# irng_2_0.net
KiCad netlist of a schematic drawn in EAGLE
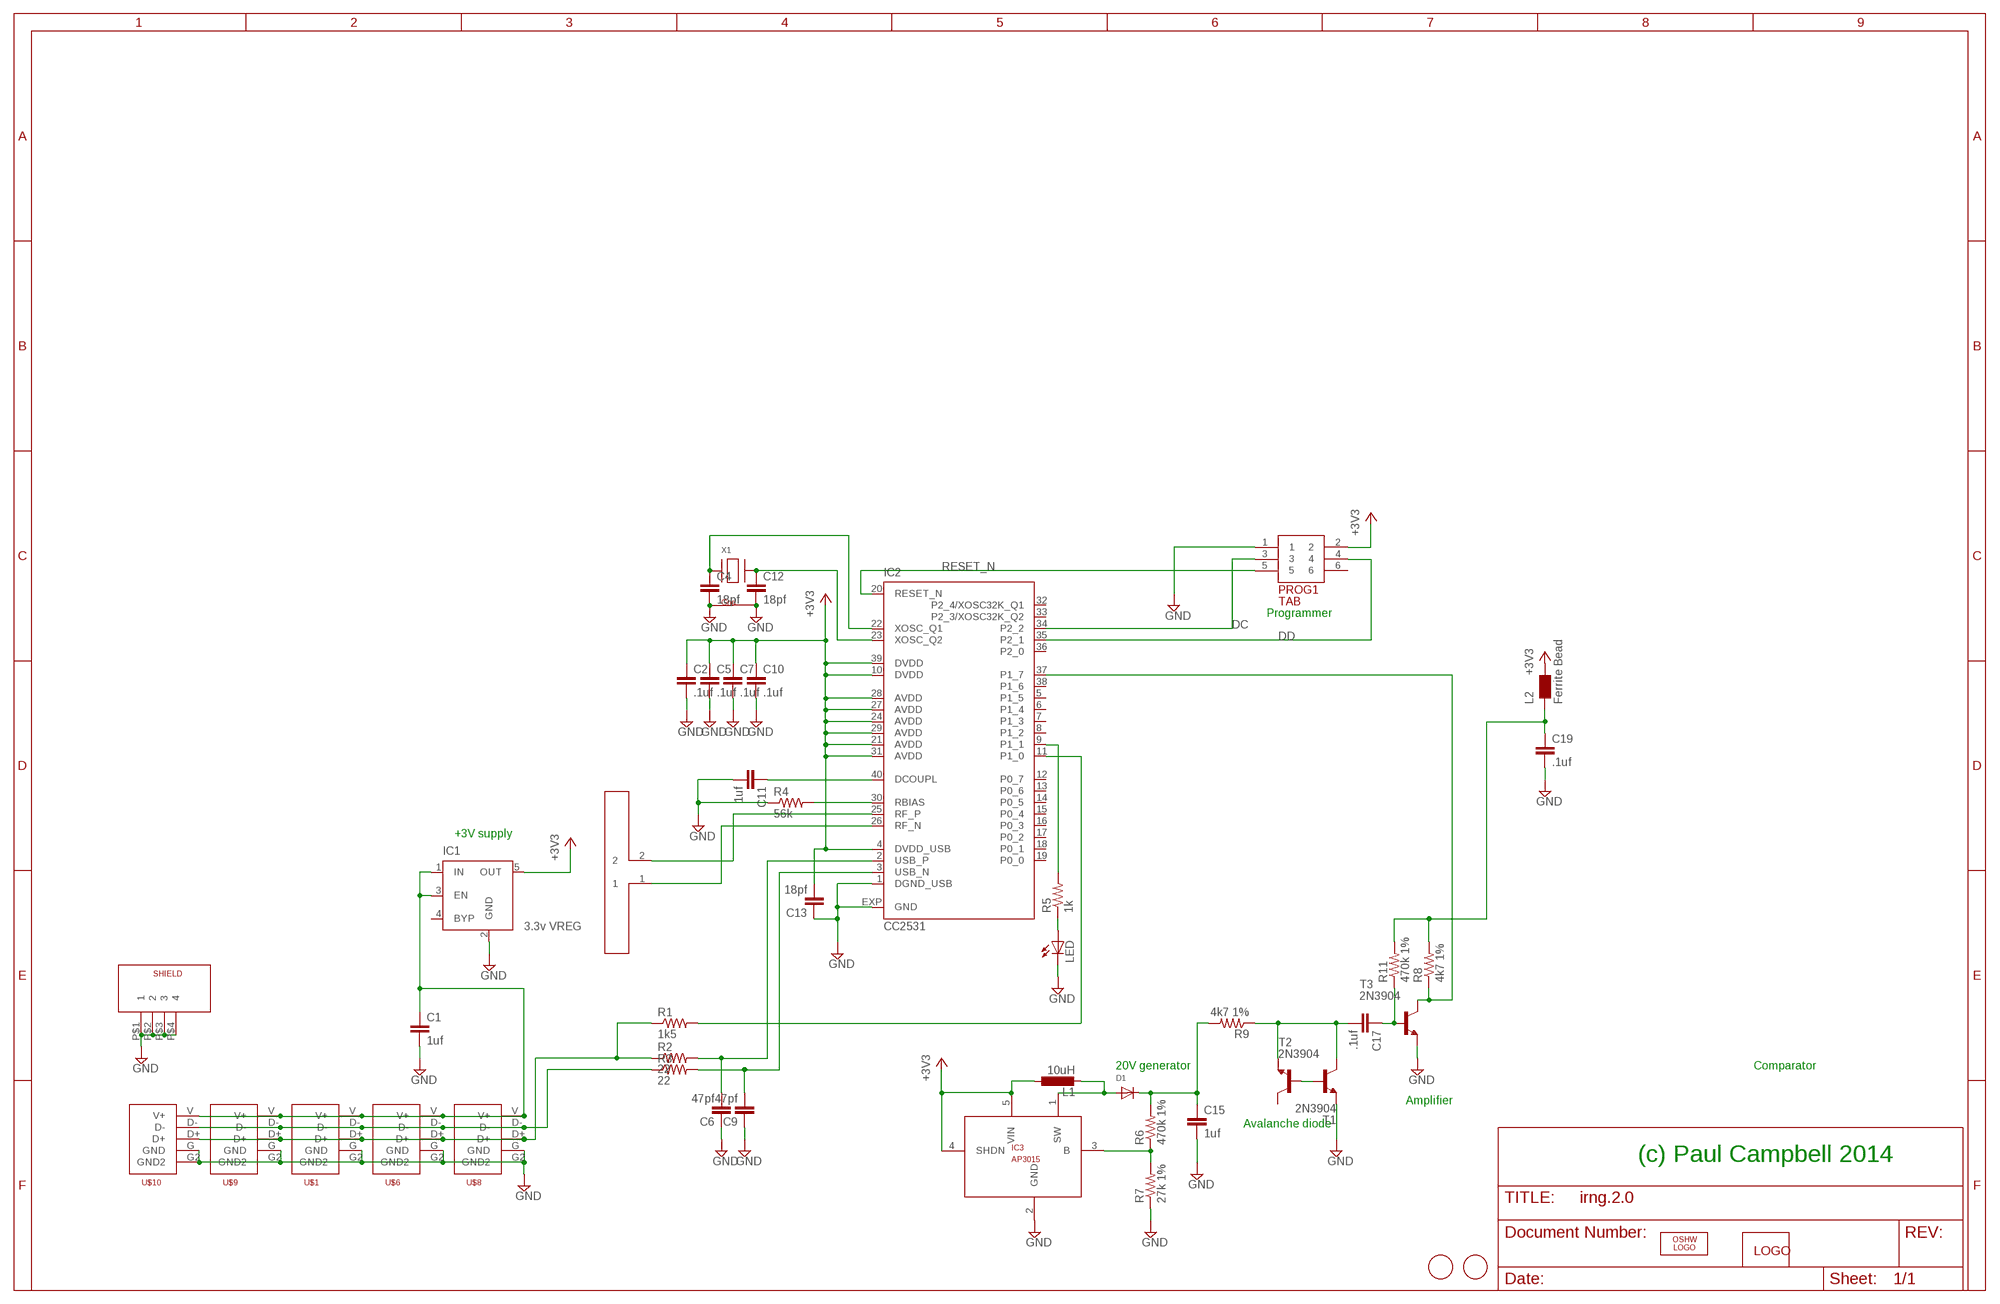
[diagram p0: schematic, sheet 1]

(export (version "E")
  (design (tool "Eeschema 10.0.6"))
  (components
    (comp (ref "C1")
      (value "1uf")
      (footprint "eagle-import:C0603")
      (libsource (lib "eagle-import") (part "C-EUC0603"))
    )
    (comp (ref "C2")
      (value ".1uf")
      (footprint "eagle-import:C0603")
      (libsource (lib "eagle-import") (part "C-EUC0603"))
    )
    (comp (ref "C4")
      (value "18pf")
      (footprint "eagle-import:C0603")
      (libsource (lib "eagle-import") (part "C-EUC0603"))
    )
    (comp (ref "C5")
      (value ".1uf")
      (footprint "eagle-import:C0603K")
      (libsource (lib "eagle-import") (part "C-EUC0603K"))
    )
    (comp (ref "C6")
      (value "47pf")
      (footprint "eagle-import:C0603")
      (libsource (lib "eagle-import") (part "C-EUC0603"))
    )
    (comp (ref "C7")
      (value ".1uf")
      (footprint "eagle-import:C0603")
      (libsource (lib "eagle-import") (part "C-EUC0603"))
    )
    (comp (ref "C9")
      (value "47pf")
      (footprint "eagle-import:C0603")
      (libsource (lib "eagle-import") (part "C-EUC0603"))
    )
    (comp (ref "C10")
      (value ".1uf")
      (footprint "eagle-import:C0603")
      (libsource (lib "eagle-import") (part "C-EUC0603"))
    )
    (comp (ref "C11")
      (value "1uf")
      (footprint "eagle-import:C0603")
      (libsource (lib "eagle-import") (part "C-EUC0603"))
    )
    (comp (ref "C12")
      (value "18pf")
      (footprint "eagle-import:C0603")
      (libsource (lib "eagle-import") (part "C-EUC0603"))
    )
    (comp (ref "C13")
      (value "18pf")
      (footprint "eagle-import:C0603")
      (libsource (lib "eagle-import") (part "C-EUC0603"))
    )
    (comp (ref "C15")
      (value "1uf")
      (footprint "eagle-import:C0603")
      (libsource (lib "eagle-import") (part "C-EUC0603"))
    )
    (comp (ref "C17")
      (value ".1uf")
      (footprint "eagle-import:C0603")
      (libsource (lib "eagle-import") (part "C-EUC0603"))
    )
    (comp (ref "C19")
      (value ".1uf")
      (footprint "eagle-import:C0603")
      (libsource (lib "eagle-import") (part "C-EUC0603"))
    )
    (comp (ref "D1")
      (value "DIODESOD-323F")
      (footprint "eagle-import:SOD-323F")
      (libsource (lib "eagle-import") (part "DIODESOD-323F"))
    )
    (comp (ref "IC1")
      (value "3.3v VREG")
      (footprint "eagle-import:SOT23-5")
      (libsource (lib "eagle-import") (part "MIC5219XX"))
    )
    (comp (ref "IC2")
      (value "CC2531")
      (footprint "eagle-import:RHA_S-PVQFN-N40")
      (fields (field (name "MPN") "CC2531F256RHAT"))
      (libsource (lib "eagle-import") (part "CC2531"))
    )
    (comp (ref "IC3")
      (value "AP3015")
      (footprint "eagle-import:SOT23-5")
      (libsource (lib "eagle-import") (part "AP3105"))
    )
    (comp (ref "L1")
      (value "10uH")
      (footprint "eagle-import:L2012C")
      (libsource (lib "eagle-import") (part "L-EUL2012C"))
    )
    (comp (ref "L2")
      (value "Ferrite Bead")
      (footprint "eagle-import:0603")
      (libsource (lib "eagle-import") (part "WE-CBF_0603"))
    )
    (comp (ref "LED")
      (value "LEDCHIP-LED0805")
      (footprint "eagle-import:CHIP-LED0805")
      (libsource (lib "eagle-import") (part "LEDCHIP-LED0805"))
    )
    (comp (ref "LOGO1")
      (value "OSHW_LOGO_FILLX0100-NT")
      (footprint "eagle-import:OSHW_FILLX100_NOTEXT")
      (libsource (lib "eagle-import") (part "OSHW_LOGO_FILLX0100-NT"))
    )
    (comp (ref "PROG1")
      (value "TAB")
      (footprint "eagle-import:TAG")
      (libsource (lib "eagle-import") (part "TAB"))
    )
    (comp (ref "R1")
      (value "1k5")
      (footprint "eagle-import:R0603")
      (libsource (lib "eagle-import") (part "R-US_R0603"))
    )
    (comp (ref "R2")
      (value "22")
      (footprint "eagle-import:R0603")
      (libsource (lib "eagle-import") (part "R-US_R0603"))
    )
    (comp (ref "R3")
      (value "22")
      (footprint "eagle-import:R0603")
      (libsource (lib "eagle-import") (part "R-US_R0603"))
    )
    (comp (ref "R4")
      (value "56k")
      (footprint "eagle-import:R0603")
      (libsource (lib "eagle-import") (part "R-US_R0603"))
    )
    (comp (ref "R5")
      (value "1k")
      (footprint "eagle-import:R0603")
      (libsource (lib "eagle-import") (part "R-US_R0603"))
    )
    (comp (ref "R6")
      (value "470k 1%")
      (footprint "eagle-import:R0603")
      (libsource (lib "eagle-import") (part "R-US_R0603"))
    )
    (comp (ref "R7")
      (value "27k 1%")
      (footprint "eagle-import:R0603")
      (libsource (lib "eagle-import") (part "R-US_R0603"))
    )
    (comp (ref "R8")
      (value "4k7 1%")
      (footprint "eagle-import:R0603")
      (libsource (lib "eagle-import") (part "R-US_R0603"))
    )
    (comp (ref "R9")
      (value "4k7 1%")
      (footprint "eagle-import:R0603")
      (libsource (lib "eagle-import") (part "R-US_R0603"))
    )
    (comp (ref "R11")
      (value "470k 1%")
      (footprint "eagle-import:R0603")
      (libsource (lib "eagle-import") (part "R-US_R0603"))
    )
    (comp (ref "T1")
      (value "2N3904")
      (footprint "eagle-import:SOT23-BEC")
      (libsource (lib "eagle-import") (part "-NPN-SOT23-BECBCF32"))
    )
    (comp (ref "T2")
      (value "2N3904")
      (footprint "eagle-import:SOT23-BEC")
      (libsource (lib "eagle-import") (part "-NPN-SOT23-BECBCF32"))
    )
    (comp (ref "T3")
      (value "2N3904")
      (footprint "eagle-import:SOT23-BEC")
      (libsource (lib "eagle-import") (part "-NPN-SOT23-BECBCF32"))
    )
    (comp (ref "U$1")
      (value "USBPAD")
      (footprint "eagle-import:PAD4")
      (libsource (lib "eagle-import") (part "USBPAD"))
    )
    (comp (ref "U$2")
      (value "DIPOLE")
      (footprint "eagle-import:YSHORT-DIPOLE")
      (libsource (lib "eagle-import") (part "DIPOLE"))
    )
    (comp (ref "U$3")
      (value "FIDUCIAL")
      (footprint "eagle-import:FIDUCIAL_1MM")
      (libsource (lib "eagle-import") (part "FIDUCIAL"))
    )
    (comp (ref "U$4")
      (value "FIDUCIAL")
      (footprint "eagle-import:FIDUCIAL_1MM")
      (libsource (lib "eagle-import") (part "FIDUCIAL"))
    )
    (comp (ref "U$5")
      (value "MOONBASE-LOGO")
      (footprint "eagle-import:MOONBASE-LOGO")
      (libsource (lib "eagle-import") (part "MOONBASE-LOGO"))
    )
    (comp (ref "U$6")
      (value "USBPAD")
      (footprint "eagle-import:PAD4")
      (libsource (lib "eagle-import") (part "USBPAD"))
    )
    (comp (ref "U$7")
      (value "SHIELD-NEW")
      (footprint "eagle-import:SHIELD-NEW")
      (libsource (lib "eagle-import") (part "SHIELD-NEW"))
    )
    (comp (ref "U$8")
      (value "USBPAD")
      (footprint "eagle-import:PAD4")
      (libsource (lib "eagle-import") (part "USBPAD"))
    )
    (comp (ref "U$9")
      (value "USBPAD")
      (footprint "eagle-import:PAD4")
      (libsource (lib "eagle-import") (part "USBPAD"))
    )
    (comp (ref "U$10")
      (value "USBPAD")
      (footprint "eagle-import:PAD4")
      (libsource (lib "eagle-import") (part "USBPAD"))
    )
    (comp (ref "X1")
      (value "XTAL-4-3225")
      (footprint "eagle-import:NX3225")
      (libsource (lib "eagle-import") (part "XTAL-4-3225"))
    )
  )
  (nets
    (net (code "1") (name "+3V3") (class "Default")
      (node (ref "C10") (pin "1") (pinfunction "1_1") (pintype "passive"))
      (node (ref "C13") (pin "2") (pinfunction "2_2") (pintype "passive"))
      (node (ref "C2") (pin "1") (pinfunction "1_1") (pintype "passive"))
      (node (ref "C5") (pin "1") (pinfunction "1_1") (pintype "passive"))
      (node (ref "C7") (pin "1") (pinfunction "1_1") (pintype "passive"))
      (node (ref "IC1") (pin "5") (pinfunction "OUT_5") (pintype "output"))
      (node (ref "IC2") (pin "10") (pinfunction "DVDD_10") (pintype "power_in"))
      (node (ref "IC2") (pin "21") (pinfunction "AVDD_21") (pintype "power_in"))
      (node (ref "IC2") (pin "24") (pinfunction "AVDD_24") (pintype "power_in"))
      (node (ref "IC2") (pin "27") (pinfunction "AVDD_27") (pintype "power_in"))
      (node (ref "IC2") (pin "28") (pinfunction "AVDD_28") (pintype "power_in"))
      (node (ref "IC2") (pin "29") (pinfunction "AVDD_29") (pintype "power_in"))
      (node (ref "IC2") (pin "31") (pinfunction "AVDD_31") (pintype "power_in"))
      (node (ref "IC2") (pin "39") (pinfunction "DVDD_39") (pintype "power_in"))
      (node (ref "IC2") (pin "4") (pinfunction "DVDD_USB_4") (pintype "power_in"))
      (node (ref "IC3") (pin "4") (pinfunction "SHDN_4") (pintype "bidirectional"))
      (node (ref "IC3") (pin "5") (pinfunction "VIN_5") (pintype "bidirectional"))
      (node (ref "L1") (pin "1") (pinfunction "1_1") (pintype "passive"))
      (node (ref "L2") (pin "2") (pinfunction "2_2") (pintype "passive"))
      (node (ref "PROG1") (pin "2") (pinfunction "2_2") (pintype "bidirectional"))
    )
    (net (code "2") (name "/DC") (class "Default")
      (node (ref "IC2") (pin "34") (pinfunction "P2_2_34") (pintype "bidirectional"))
      (node (ref "PROG1") (pin "3") (pinfunction "3_3") (pintype "bidirectional"))
    )
    (net (code "3") (name "/DD") (class "Default")
      (node (ref "IC2") (pin "35") (pinfunction "P2_1_35") (pintype "bidirectional"))
      (node (ref "PROG1") (pin "4") (pinfunction "4_4") (pintype "bidirectional"))
    )
    (net (code "4") (name "/RESET_N") (class "Default")
      (node (ref "IC2") (pin "20") (pinfunction "RESET_N_20") (pintype "input"))
      (node (ref "PROG1") (pin "5") (pinfunction "5_5") (pintype "bidirectional"))
    )
    (net (code "5") (name "GND") (class "Default")
      (node (ref "C1") (pin "2") (pinfunction "2_2") (pintype "passive"))
      (node (ref "C10") (pin "2") (pinfunction "2_2") (pintype "passive"))
      (node (ref "C11") (pin "2") (pinfunction "2_2") (pintype "passive"))
      (node (ref "C12") (pin "2") (pinfunction "2_2") (pintype "passive"))
      (node (ref "C13") (pin "1") (pinfunction "1_1") (pintype "passive"))
      (node (ref "C15") (pin "2") (pinfunction "2_2") (pintype "passive"))
      (node (ref "C19") (pin "2") (pinfunction "2_2") (pintype "passive"))
      (node (ref "C2") (pin "2") (pinfunction "2_2") (pintype "passive"))
      (node (ref "C4") (pin "2") (pinfunction "2_2") (pintype "passive"))
      (node (ref "C5") (pin "2") (pinfunction "2_2") (pintype "passive"))
      (node (ref "C6") (pin "1") (pinfunction "1_1") (pintype "passive"))
      (node (ref "C7") (pin "2") (pinfunction "2_2") (pintype "passive"))
      (node (ref "C9") (pin "1") (pinfunction "1_1") (pintype "passive"))
      (node (ref "IC1") (pin "2") (pinfunction "GND_2") (pintype "power_in"))
      (node (ref "IC2") (pin "1") (pinfunction "DGND_USB_1") (pintype "power_in"))
      (node (ref "IC2") (pin "EXP") (pinfunction "GND_EXP") (pintype "passive"))
      (node (ref "IC3") (pin "2") (pinfunction "GND_2") (pintype "bidirectional"))
      (node (ref "LED") (pin "C") (pinfunction "C_C") (pintype "passive"))
      (node (ref "PROG1") (pin "1") (pinfunction "1_1") (pintype "bidirectional"))
      (node (ref "R4") (pin "1") (pinfunction "1_1") (pintype "passive"))
      (node (ref "R7") (pin "1") (pinfunction "1_1") (pintype "passive"))
      (node (ref "T2") (pin "E") (pinfunction "E_E") (pintype "passive"))
      (node (ref "T3") (pin "E") (pinfunction "E_E") (pintype "passive"))
      (node (ref "U$1") (pin "G") (pinfunction "GND_G") (pintype "bidirectional"))
      (node (ref "U$1") (pin "G2") (pinfunction "GND2_G2") (pintype "bidirectional"))
      (node (ref "U$10") (pin "G") (pinfunction "GND_G") (pintype "bidirectional"))
      (node (ref "U$10") (pin "G2") (pinfunction "GND2_G2") (pintype "bidirectional"))
      (node (ref "U$6") (pin "G") (pinfunction "GND_G") (pintype "bidirectional"))
      (node (ref "U$6") (pin "G2") (pinfunction "GND2_G2") (pintype "bidirectional"))
      (node (ref "U$7") (pin "P$1") (pinfunction "1_P$1") (pintype "bidirectional"))
      (node (ref "U$7") (pin "P$2") (pinfunction "2_P$2") (pintype "bidirectional"))
      (node (ref "U$7") (pin "P$3") (pinfunction "3_P$3") (pintype "bidirectional"))
      (node (ref "U$7") (pin "P$4") (pinfunction "4_P$4") (pintype "bidirectional"))
      (node (ref "U$8") (pin "G") (pinfunction "GND_G") (pintype "bidirectional"))
      (node (ref "U$8") (pin "G2") (pinfunction "GND2_G2") (pintype "bidirectional"))
      (node (ref "U$9") (pin "G") (pinfunction "GND_G") (pintype "bidirectional"))
      (node (ref "U$9") (pin "G2") (pinfunction "GND2_G2") (pintype "bidirectional"))
      (node (ref "X1") (pin "2") (pinfunction "G2_2") (pintype "power_in"))
      (node (ref "X1") (pin "4") (pinfunction "G1_4") (pintype "power_in"))
    )
    (net (code "6") (name "Net-(C15-Pad1)") (class "Default")
      (node (ref "C15") (pin "1") (pinfunction "1_1") (pintype "passive"))
      (node (ref "D1") (pin "C") (pinfunction "C_C") (pintype "passive"))
      (node (ref "R6") (pin "2") (pinfunction "2_2") (pintype "passive"))
      (node (ref "R9") (pin "2") (pinfunction "2_2") (pintype "passive"))
    )
    (net (code "7") (name "Net-(C17-Pad1)") (class "Default")
      (node (ref "C17") (pin "1") (pinfunction "1_1") (pintype "passive"))
      (node (ref "R11") (pin "1") (pinfunction "1_1") (pintype "passive"))
      (node (ref "T3") (pin "B") (pinfunction "B_B") (pintype "passive"))
    )
    (net (code "8") (name "Net-(C17-Pad2)") (class "Default")
      (node (ref "C17") (pin "2") (pinfunction "2_2") (pintype "passive"))
      (node (ref "R9") (pin "1") (pinfunction "1_1") (pintype "passive"))
      (node (ref "T1") (pin "E") (pinfunction "E_E") (pintype "passive"))
      (node (ref "T2") (pin "C") (pinfunction "C_C") (pintype "passive"))
    )
    (net (code "9") (name "Net-(C19-Pad1)") (class "Default")
      (node (ref "C19") (pin "1") (pinfunction "1_1") (pintype "passive"))
      (node (ref "L2") (pin "1") (pinfunction "1_1") (pintype "passive"))
      (node (ref "R11") (pin "2") (pinfunction "2_2") (pintype "passive"))
      (node (ref "R8") (pin "2") (pinfunction "2_2") (pintype "passive"))
    )
    (net (code "10") (name "Net-(IC1-EN)") (class "Default")
      (node (ref "C1") (pin "1") (pinfunction "1_1") (pintype "passive"))
      (node (ref "IC1") (pin "1") (pinfunction "IN_1") (pintype "input"))
      (node (ref "IC1") (pin "3") (pinfunction "EN_3") (pintype "input"))
      (node (ref "U$1") (pin "V") (pinfunction "V+_V") (pintype "bidirectional"))
      (node (ref "U$10") (pin "V") (pinfunction "V+_V") (pintype "bidirectional"))
      (node (ref "U$6") (pin "V") (pinfunction "V+_V") (pintype "bidirectional"))
      (node (ref "U$8") (pin "V") (pinfunction "V+_V") (pintype "bidirectional"))
      (node (ref "U$9") (pin "V") (pinfunction "V+_V") (pintype "bidirectional"))
    )
    (net (code "11") (name "Net-(IC2-DCOUPL)") (class "Default")
      (node (ref "C11") (pin "1") (pinfunction "1_1") (pintype "passive"))
      (node (ref "IC2") (pin "40") (pinfunction "DCOUPL_40") (pintype "power_in"))
    )
    (net (code "12") (name "Net-(IC2-P1_0)") (class "Default")
      (node (ref "IC2") (pin "11") (pinfunction "P1_0_11") (pintype "bidirectional"))
      (node (ref "R1") (pin "2") (pinfunction "2_2") (pintype "passive"))
    )
    (net (code "13") (name "Net-(IC2-P1_1)") (class "Default")
      (node (ref "IC2") (pin "9") (pinfunction "P1_1_9") (pintype "bidirectional"))
      (node (ref "R5") (pin "2") (pinfunction "2_2") (pintype "passive"))
    )
    (net (code "14") (name "Net-(IC2-P1_7)") (class "Default")
      (node (ref "IC2") (pin "37") (pinfunction "P1_7_37") (pintype "bidirectional"))
      (node (ref "R8") (pin "1") (pinfunction "1_1") (pintype "passive"))
      (node (ref "T3") (pin "C") (pinfunction "C_C") (pintype "passive"))
    )
    (net (code "15") (name "Net-(IC2-RBIAS)") (class "Default")
      (node (ref "IC2") (pin "30") (pinfunction "RBIAS_30") (pintype "bidirectional"))
      (node (ref "R4") (pin "2") (pinfunction "2_2") (pintype "passive"))
    )
    (net (code "16") (name "Net-(IC2-RF_N)") (class "Default")
      (node (ref "IC2") (pin "26") (pinfunction "RF_N_26") (pintype "bidirectional"))
      (node (ref "U$2") (pin "1") (pinfunction "1_1") (pintype "bidirectional"))
    )
    (net (code "17") (name "Net-(IC2-RF_P)") (class "Default")
      (node (ref "IC2") (pin "25") (pinfunction "RF_P_25") (pintype "bidirectional"))
      (node (ref "U$2") (pin "2") (pinfunction "2_2") (pintype "bidirectional"))
    )
    (net (code "18") (name "Net-(IC2-USB_N)") (class "Default")
      (node (ref "C9") (pin "2") (pinfunction "2_2") (pintype "passive"))
      (node (ref "IC2") (pin "3") (pinfunction "USB_N_3") (pintype "bidirectional"))
      (node (ref "R3") (pin "2") (pinfunction "2_2") (pintype "passive"))
    )
    (net (code "19") (name "Net-(IC2-USB_P)") (class "Default")
      (node (ref "C6") (pin "2") (pinfunction "2_2") (pintype "passive"))
      (node (ref "IC2") (pin "2") (pinfunction "USB_P_2") (pintype "bidirectional"))
      (node (ref "R2") (pin "2") (pinfunction "2_2") (pintype "passive"))
    )
    (net (code "20") (name "Net-(IC2-XOSC_Q1)") (class "Default")
      (node (ref "C4") (pin "1") (pinfunction "1_1") (pintype "passive"))
      (node (ref "IC2") (pin "22") (pinfunction "XOSC_Q1_22") (pintype "bidirectional"))
      (node (ref "X1") (pin "1") (pinfunction "X1_1") (pintype "bidirectional"))
    )
    (net (code "21") (name "Net-(IC2-XOSC_Q2)") (class "Default")
      (node (ref "C12") (pin "1") (pinfunction "1_1") (pintype "passive"))
      (node (ref "IC2") (pin "23") (pinfunction "XOSC_Q2_23") (pintype "bidirectional"))
      (node (ref "X1") (pin "3") (pinfunction "X2_3") (pintype "bidirectional"))
    )
    (net (code "22") (name "Net-(IC3-B)") (class "Default")
      (node (ref "IC3") (pin "3") (pinfunction "B_3") (pintype "bidirectional"))
      (node (ref "R6") (pin "1") (pinfunction "1_1") (pintype "passive"))
      (node (ref "R7") (pin "2") (pinfunction "2_2") (pintype "passive"))
    )
    (net (code "23") (name "Net-(IC3-SW)") (class "Default")
      (node (ref "D1") (pin "A") (pinfunction "A_A") (pintype "passive"))
      (node (ref "IC3") (pin "1") (pinfunction "SW_1") (pintype "bidirectional"))
      (node (ref "L1") (pin "2") (pinfunction "2_2") (pintype "passive"))
    )
    (net (code "24") (name "Net-(LED-PadA)") (class "Default")
      (node (ref "LED") (pin "A") (pinfunction "A_A") (pintype "passive"))
      (node (ref "R5") (pin "1") (pinfunction "1_1") (pintype "passive"))
    )
    (net (code "25") (name "Net-(R1-Pad1)") (class "Default")
      (node (ref "R1") (pin "1") (pinfunction "1_1") (pintype "passive"))
      (node (ref "R2") (pin "1") (pinfunction "1_1") (pintype "passive"))
      (node (ref "U$1") (pin "D+") (pinfunction "D+_D+") (pintype "bidirectional"))
      (node (ref "U$10") (pin "D+") (pinfunction "D+_D+") (pintype "bidirectional"))
      (node (ref "U$6") (pin "D+") (pinfunction "D+_D+") (pintype "bidirectional"))
      (node (ref "U$8") (pin "D+") (pinfunction "D+_D+") (pintype "bidirectional"))
      (node (ref "U$9") (pin "D+") (pinfunction "D+_D+") (pintype "bidirectional"))
    )
    (net (code "26") (name "Net-(R3-Pad1)") (class "Default")
      (node (ref "R3") (pin "1") (pinfunction "1_1") (pintype "passive"))
      (node (ref "U$1") (pin "D-") (pinfunction "D-_D-") (pintype "bidirectional"))
      (node (ref "U$10") (pin "D-") (pinfunction "D-_D-") (pintype "bidirectional"))
      (node (ref "U$6") (pin "D-") (pinfunction "D-_D-") (pintype "bidirectional"))
      (node (ref "U$8") (pin "D-") (pinfunction "D-_D-") (pintype "bidirectional"))
      (node (ref "U$9") (pin "D-") (pinfunction "D-_D-") (pintype "bidirectional"))
    )
    (net (code "27") (name "Net-(T1-PadB)") (class "Default")
      (node (ref "T1") (pin "B") (pinfunction "B_B") (pintype "passive"))
      (node (ref "T2") (pin "B") (pinfunction "B_B") (pintype "passive"))
    )
    (net (code "28") (name "unconnected-(IC1-BYP-Pad4)") (class "Default")
      (node (ref "IC1") (pin "4") (pinfunction "BYP_4") (pintype "passive"))
    )
    (net (code "29") (name "unconnected-(IC2-P0_0-Pad19)") (class "Default")
      (node (ref "IC2") (pin "19") (pinfunction "P0_0_19") (pintype "bidirectional"))
    )
    (net (code "30") (name "unconnected-(IC2-P0_1-Pad18)") (class "Default")
      (node (ref "IC2") (pin "18") (pinfunction "P0_1_18") (pintype "bidirectional"))
    )
    (net (code "31") (name "unconnected-(IC2-P0_2-Pad17)") (class "Default")
      (node (ref "IC2") (pin "17") (pinfunction "P0_2_17") (pintype "bidirectional"))
    )
    (net (code "32") (name "unconnected-(IC2-P0_3-Pad16)") (class "Default")
      (node (ref "IC2") (pin "16") (pinfunction "P0_3_16") (pintype "bidirectional"))
    )
    (net (code "33") (name "unconnected-(IC2-P0_4-Pad15)") (class "Default")
      (node (ref "IC2") (pin "15") (pinfunction "P0_4_15") (pintype "bidirectional"))
    )
    (net (code "34") (name "unconnected-(IC2-P0_5-Pad14)") (class "Default")
      (node (ref "IC2") (pin "14") (pinfunction "P0_5_14") (pintype "bidirectional"))
    )
    (net (code "35") (name "unconnected-(IC2-P0_6-Pad13)") (class "Default")
      (node (ref "IC2") (pin "13") (pinfunction "P0_6_13") (pintype "bidirectional"))
    )
    (net (code "36") (name "unconnected-(IC2-P0_7-Pad12)") (class "Default")
      (node (ref "IC2") (pin "12") (pinfunction "P0_7_12") (pintype "bidirectional"))
    )
    (net (code "37") (name "unconnected-(IC2-P1_2-Pad8)") (class "Default")
      (node (ref "IC2") (pin "8") (pinfunction "P1_2_8") (pintype "bidirectional"))
    )
    (net (code "38") (name "unconnected-(IC2-P1_3-Pad7)") (class "Default")
      (node (ref "IC2") (pin "7") (pinfunction "P1_3_7") (pintype "bidirectional"))
    )
    (net (code "39") (name "unconnected-(IC2-P1_4-Pad6)") (class "Default")
      (node (ref "IC2") (pin "6") (pinfunction "P1_4_6") (pintype "bidirectional"))
    )
    (net (code "40") (name "unconnected-(IC2-P1_5-Pad5)") (class "Default")
      (node (ref "IC2") (pin "5") (pinfunction "P1_5_5") (pintype "bidirectional"))
    )
    (net (code "41") (name "unconnected-(IC2-P1_6-Pad38)") (class "Default")
      (node (ref "IC2") (pin "38") (pinfunction "P1_6_38") (pintype "bidirectional"))
    )
    (net (code "42") (name "unconnected-(IC2-P2_0-Pad36)") (class "Default")
      (node (ref "IC2") (pin "36") (pinfunction "P2_0_36") (pintype "bidirectional"))
    )
    (net (code "43") (name "unconnected-(IC2-P2_3{slash}XOSC32K_Q2-Pad33)") (class "Default")
      (node (ref "IC2") (pin "33") (pinfunction "P2_3/XOSC32K_Q2_33") (pintype "bidirectional"))
    )
    (net (code "44") (name "unconnected-(IC2-P2_4{slash}XOSC32K_Q1-Pad32)") (class "Default")
      (node (ref "IC2") (pin "32") (pinfunction "P2_4/XOSC32K_Q1_32") (pintype "bidirectional"))
    )
    (net (code "45") (name "unconnected-(PROG1-Pad6)") (class "Default")
      (node (ref "PROG1") (pin "6") (pinfunction "6_6") (pintype "bidirectional"))
    )
    (net (code "46") (name "unconnected-(T1-PadC)") (class "Default")
      (node (ref "T1") (pin "C") (pinfunction "C_C") (pintype "passive"))
    )
  )
)
